# MPPT_Charger_12A.net
KiCad netlist of a schematic drawn in EAGLE
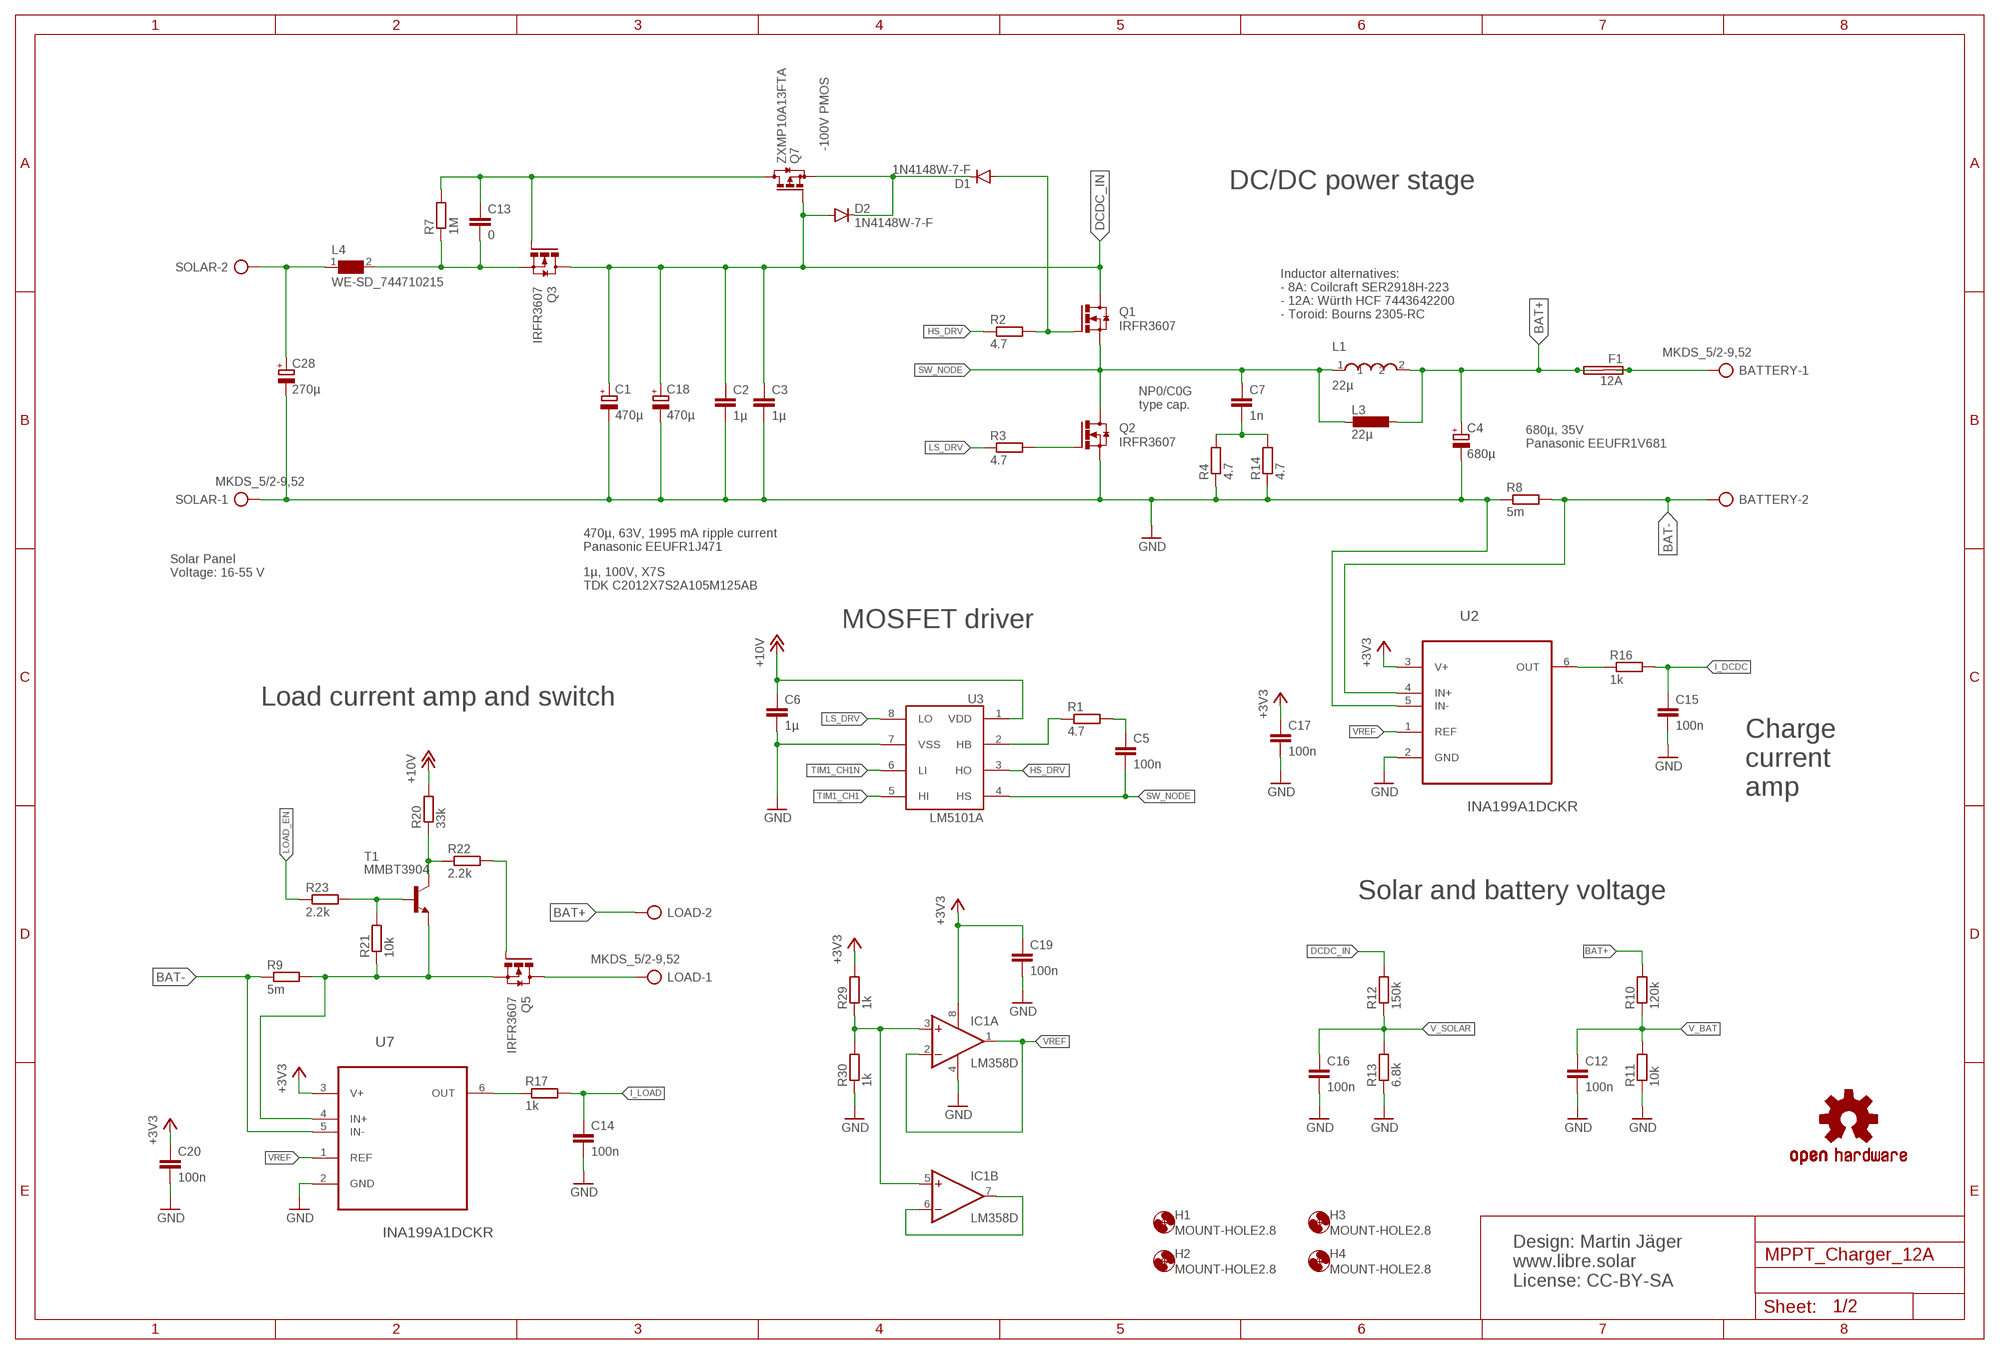
[diagram p0: schematic, sheet 1]
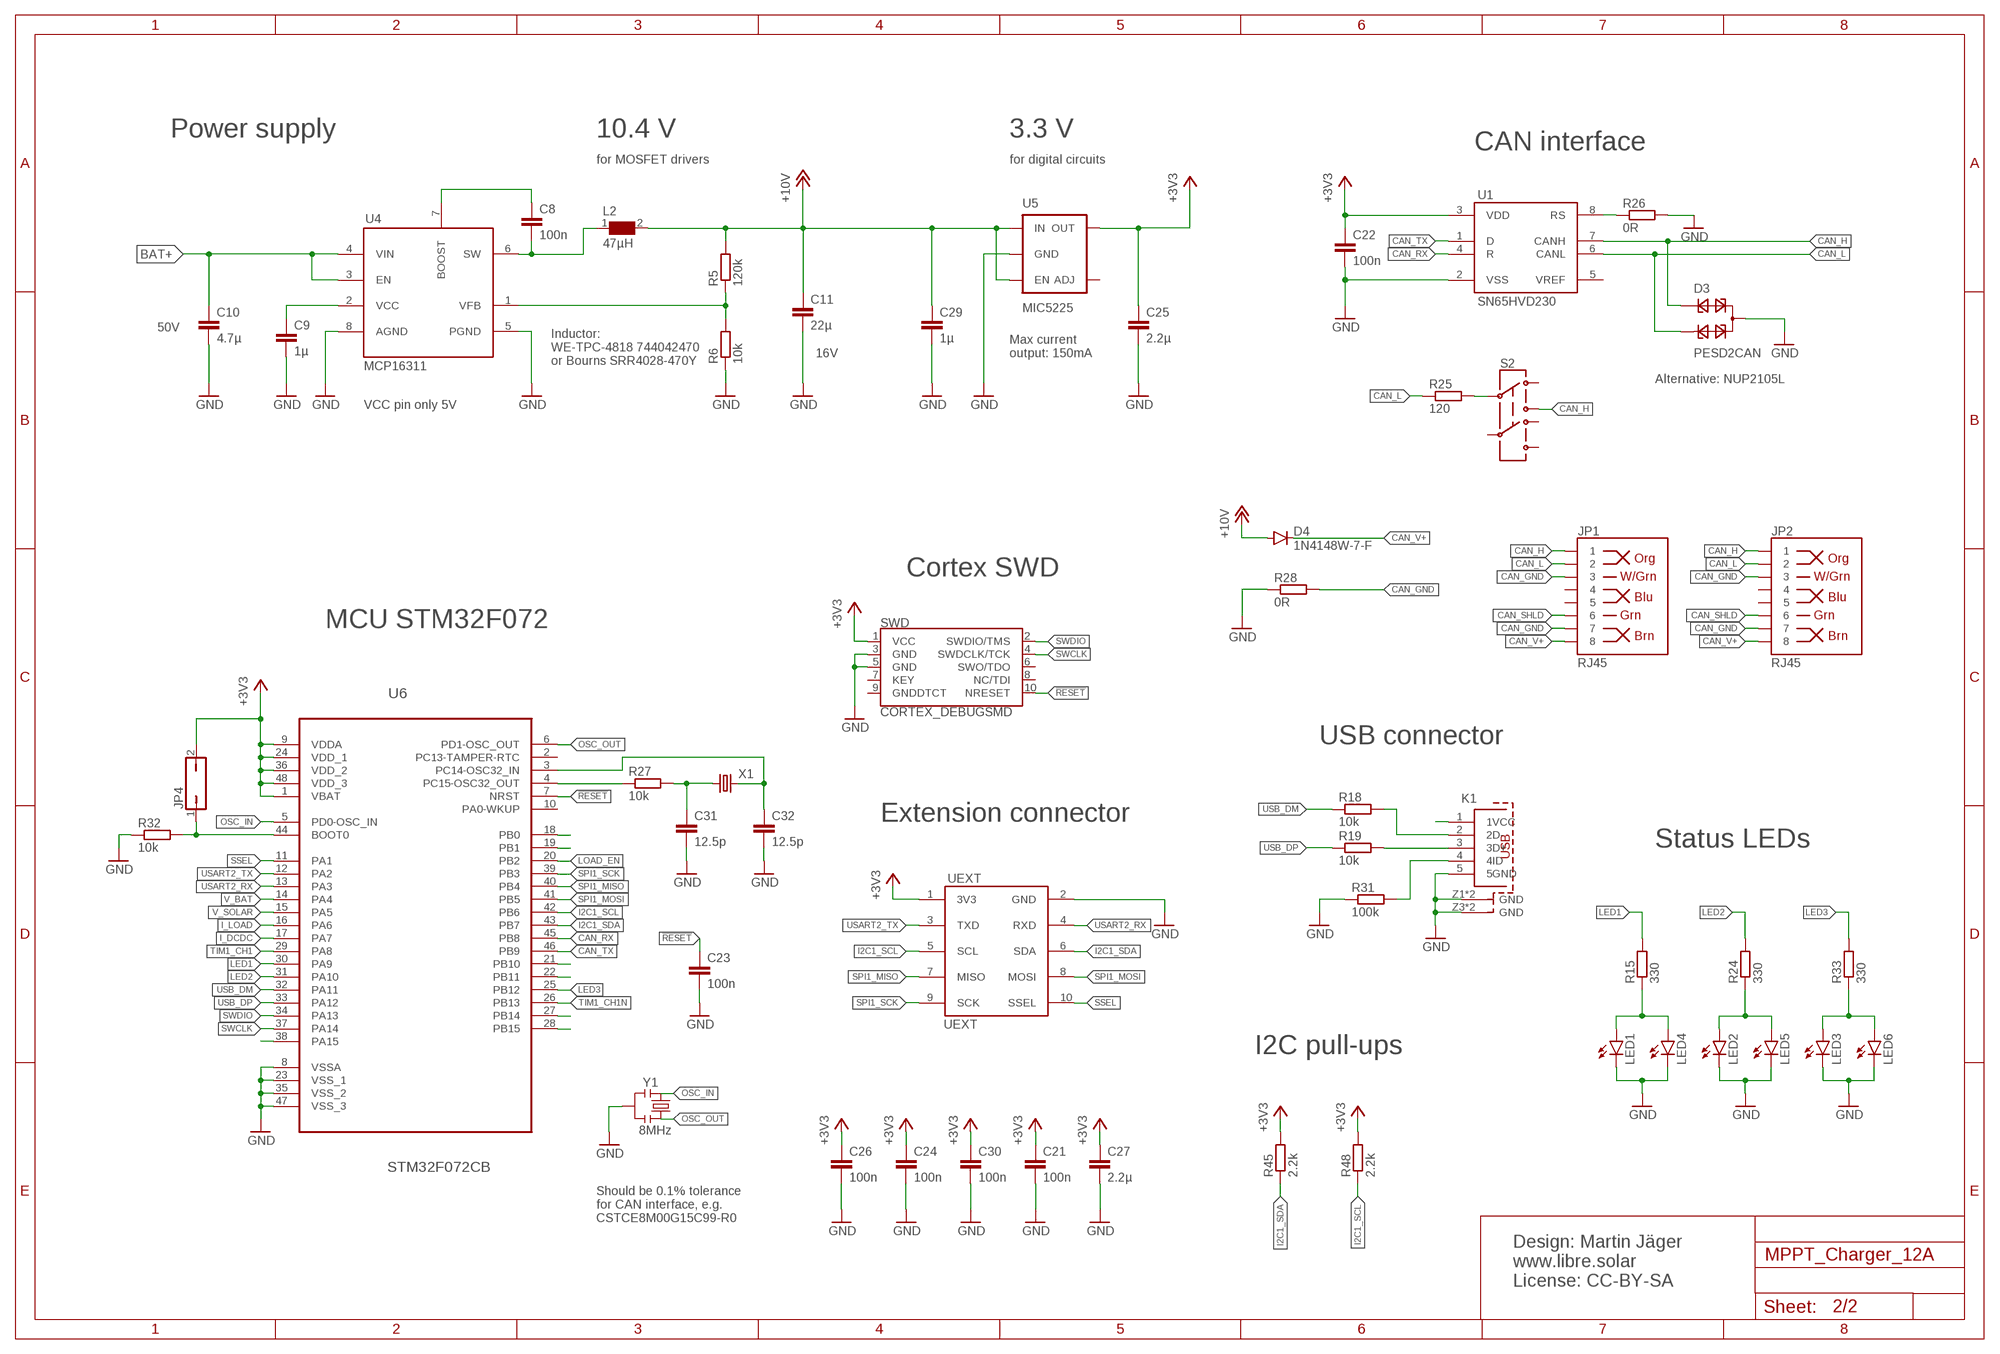
[diagram p1: schematic, sheet 2]

(export (version "E")
  (design (tool "Eeschema 10.0.6"))
  (components
    (comp (ref "C8")
      (value "100n")
      (footprint "eagle-import:C0603")
      (fields (field (name "MF") "MURATA") (field (name "MPN") "GRM188R71H104KA93D"))
      (libsource (lib "eagle-import") (part "C-EUC0603"))
    )
    (comp (ref "C9")
      (value "1µ")
      (footprint "eagle-import:C0603")
      (fields (field (name "MF") "AVX") (field (name "MPN") "08055C104KAT2A"))
      (libsource (lib "eagle-import") (part "C-EUC0603"))
    )
    (comp (ref "C10")
      (value "4.7µ")
      (footprint "eagle-import:C1210")
      (fields (field (name "MF") "MURATA") (field (name "MPN") "GRM31CR71H475KA12L"))
      (libsource (lib "eagle-import") (part "C-EUC1210"))
    )
    (comp (ref "C11")
      (value "22µ")
      (footprint "eagle-import:C1210")
      (fields (field (name "MF") "MULTICOMP") (field (name "MPN") "MC1210B226M160CT"))
      (libsource (lib "eagle-import") (part "C-EUC1210"))
    )
    (comp (ref "C21")
      (value "100n")
      (footprint "eagle-import:C0603")
      (fields (field (name "MF") "MURATA") (field (name "MPN") "GRM188R71H104KA93D"))
      (libsource (lib "eagle-import") (part "C-EUC0603"))
    )
    (comp (ref "C22")
      (value "100n")
      (footprint "eagle-import:C0603")
      (fields (field (name "MF") "AVX") (field (name "MPN") "06035C104KAT2A"))
      (libsource (lib "eagle-import") (part "C-EUC0603"))
    )
    (comp (ref "C23")
      (value "100n")
      (footprint "eagle-import:C0603")
      (fields (field (name "MF") "MURATA") (field (name "MPN") "GRM188R71H104KA93D"))
      (libsource (lib "eagle-import") (part "C-EUC0603"))
    )
    (comp (ref "C24")
      (value "100n")
      (footprint "eagle-import:C0603")
      (fields (field (name "MF") "MURATA") (field (name "MPN") "GRM188R71H104KA93D"))
      (libsource (lib "eagle-import") (part "C-EUC0603"))
    )
    (comp (ref "C25")
      (value "2.2µ")
      (footprint "eagle-import:C0603")
      (fields (field (name "MF") "AVX") (field (name "MPN") "0805YC475KAT2A"))
      (libsource (lib "eagle-import") (part "C-EUC0603"))
    )
    (comp (ref "C26")
      (value "100n")
      (footprint "eagle-import:C0603")
      (fields (field (name "MF") "MURATA") (field (name "MPN") "GRM188R71H104KA93D"))
      (libsource (lib "eagle-import") (part "C-EUC0603"))
    )
    (comp (ref "C27")
      (value "2.2µ")
      (footprint "eagle-import:C0603")
      (fields (field (name "MF") "AVX") (field (name "MPN") "0805YC475KAT2A"))
      (libsource (lib "eagle-import") (part "C-EUC0603"))
    )
    (comp (ref "C29")
      (value "1µ")
      (footprint "eagle-import:C0603")
      (fields (field (name "MF") "AVX") (field (name "MPN") "08055C104KAT2A"))
      (libsource (lib "eagle-import") (part "C-EUC0603"))
    )
    (comp (ref "C30")
      (value "100n")
      (footprint "eagle-import:C0603")
      (fields (field (name "MF") "MURATA") (field (name "MPN") "GRM188R71H104KA93D"))
      (libsource (lib "eagle-import") (part "C-EUC0603"))
    )
    (comp (ref "C31")
      (value "12.5p")
      (footprint "eagle-import:C0603")
      (fields (field (name "MF") "MURATA") (field (name "MPN") "GRM188R71H104KA93D"))
      (libsource (lib "eagle-import") (part "C-EUC0603"))
    )
    (comp (ref "C32")
      (value "12.5p")
      (footprint "eagle-import:C0603")
      (fields (field (name "MF") "MURATA") (field (name "MPN") "GRM188R71H104KA93D"))
      (libsource (lib "eagle-import") (part "C-EUC0603"))
    )
    (comp (ref "D3")
      (value "PESD2CAN")
      (footprint "eagle-import:SOT23")
      (fields (field (name "MF") "NXP"))
      (libsource (lib "eagle-import") (part "PESD2CAN"))
    )
    (comp (ref "D4")
      (value "1N4148W-7-F")
      (footprint "eagle-import:SOD-123")
      (fields (field (name "MF") "MULTICOMP") (field (name "MPN") "1N4148W"))
      (libsource (lib "eagle-import") (part "DIODESOD123"))
    )
    (comp (ref "JP1")
      (value "RJ45")
      (footprint "eagle-import:RJ45-8")
      (fields (field (name "MF") "AMPHENOL COMMERCIAL PRODUCTS") (field (name "MPN") "RJHSE-5080"))
      (libsource (lib "eagle-import") (part "RJ45-8PTH"))
    )
    (comp (ref "JP2")
      (value "RJ45")
      (footprint "eagle-import:RJ45-8")
      (fields (field (name "MF") "AMPHENOL COMMERCIAL PRODUCTS") (field (name "MPN") "RJHSE-5080"))
      (libsource (lib "eagle-import") (part "RJ45-8PTH"))
    )
    (comp (ref "JP4")
      (value "JP1Q")
      (footprint "eagle-import:JP1")
      (libsource (lib "eagle-import") (part "JP1Q"))
    )
    (comp (ref "K1")
      (value "629105150521")
      (footprint "eagle-import:629105150521")
      (libsource (lib "eagle-import") (part "629105150521"))
    )
    (comp (ref "L2")
      (value "47µH")
      (footprint "eagle-import:WE-TPC_4818_4828")
      (fields (field (name "MF") "WURTH ELEKTRONIK") (field (name "MPN") "744043470"))
      (libsource (lib "eagle-import") (part "WE-TPC_4818/4828"))
    )
    (comp (ref "LED1")
      (value "LED3MM")
      (footprint "eagle-import:LED3MM")
      (libsource (lib "eagle-import") (part "LED3MM"))
    )
    (comp (ref "LED2")
      (value "LED3MM")
      (footprint "eagle-import:LED3MM")
      (libsource (lib "eagle-import") (part "LED3MM"))
    )
    (comp (ref "LED3")
      (value "LED3MM")
      (footprint "eagle-import:LED3MM")
      (libsource (lib "eagle-import") (part "LED3MM"))
    )
    (comp (ref "LED4")
      (value "LED0603")
      (footprint "eagle-import:LED-0603")
      (libsource (lib "eagle-import") (part "LED0603"))
    )
    (comp (ref "LED5")
      (value "LED0603")
      (footprint "eagle-import:LED-0603")
      (libsource (lib "eagle-import") (part "LED0603"))
    )
    (comp (ref "LED6")
      (value "LED0603")
      (footprint "eagle-import:LED-0603")
      (libsource (lib "eagle-import") (part "LED0603"))
    )
    (comp (ref "R5")
      (value "120k")
      (footprint "eagle-import:R0603")
      (fields (field (name "MF") "YAGEO (PHYCOMP)") (field (name "MPN") "RC0603FR-07120KL"))
      (libsource (lib "eagle-import") (part "R-EU_R0603"))
    )
    (comp (ref "R6")
      (value "10k")
      (footprint "eagle-import:R0603")
      (fields (field (name "MF") "YAGEO (PHYCOMP)") (field (name "MPN") "RC0603FR-0710KL"))
      (libsource (lib "eagle-import") (part "R-EU_R0603"))
    )
    (comp (ref "R15")
      (value "330")
      (footprint "eagle-import:R0603")
      (fields (field (name "MF") "YAGEO (PHYCOMP)") (field (name "MPN") "RC0603FR-07330RL"))
      (libsource (lib "eagle-import") (part "R-EU_R0603"))
    )
    (comp (ref "R18")
      (value "10k")
      (footprint "eagle-import:R0603")
      (fields (field (name "MF") "YAGEO (PHYCOMP)") (field (name "MPN") "RC0603FR-0710KL"))
      (libsource (lib "eagle-import") (part "R-EU_R0603"))
    )
    (comp (ref "R19")
      (value "10k")
      (footprint "eagle-import:R0603")
      (fields (field (name "MF") "YAGEO (PHYCOMP)") (field (name "MPN") "RC0603FR-0710KL"))
      (libsource (lib "eagle-import") (part "R-EU_R0603"))
    )
    (comp (ref "R24")
      (value "330")
      (footprint "eagle-import:R0603")
      (fields (field (name "MF") "YAGEO (PHYCOMP)") (field (name "MPN") "RC0603FR-07330RL"))
      (libsource (lib "eagle-import") (part "R-EU_R0603"))
    )
    (comp (ref "R25")
      (value "120")
      (footprint "eagle-import:R1206")
      (fields (field (name "MF") "WELWYN") (field (name "MPN") "WCR0805-120RFI"))
      (libsource (lib "eagle-import") (part "R-EU_R1206"))
    )
    (comp (ref "R26")
      (value "0R")
      (footprint "eagle-import:R0603")
      (fields (field (name "MF") "PANASONIC ELECTRONIC COMPONENTS") (field (name "MPN") "ERJ3GEY0R00V"))
      (libsource (lib "eagle-import") (part "R-EU_R0603"))
    )
    (comp (ref "R27")
      (value "10k")
      (footprint "eagle-import:R0603")
      (fields (field (name "MF") "YAGEO (PHYCOMP)") (field (name "MPN") "RC0603FR-0710KL"))
      (libsource (lib "eagle-import") (part "R-EU_R0603"))
    )
    (comp (ref "R28")
      (value "0R")
      (footprint "eagle-import:R0603")
      (fields (field (name "MF") "PANASONIC ELECTRONIC COMPONENTS") (field (name "MPN") "ERJ3GEY0R00V"))
      (libsource (lib "eagle-import") (part "R-EU_R0603"))
    )
    (comp (ref "R31")
      (value "100k")
      (footprint "eagle-import:R0603")
      (fields (field (name "MF") "YAGEO (PHYCOMP)") (field (name "MPN") "RC0603FR-0710KL"))
      (libsource (lib "eagle-import") (part "R-EU_R0603"))
    )
    (comp (ref "R32")
      (value "10k")
      (footprint "eagle-import:R0603")
      (fields (field (name "MF") "YAGEO (PHYCOMP)") (field (name "MPN") "RC0603FR-0710KL"))
      (libsource (lib "eagle-import") (part "R-EU_R0603"))
    )
    (comp (ref "R33")
      (value "330")
      (footprint "eagle-import:R0603")
      (fields (field (name "MF") "YAGEO (PHYCOMP)") (field (name "MPN") "RC0603FR-07330RL"))
      (libsource (lib "eagle-import") (part "R-EU_R0603"))
    )
    (comp (ref "R45")
      (value "2.2k")
      (footprint "eagle-import:R0603")
      (fields (field (name "MF") "YAGEO (PHYCOMP)") (field (name "MPN") "RC0603FR-072K2L."))
      (libsource (lib "eagle-import") (part "R-EU_R0603"))
    )
    (comp (ref "R48")
      (value "2.2k")
      (footprint "eagle-import:R0603")
      (fields (field (name "MF") "YAGEO (PHYCOMP)") (field (name "MPN") "RC0603FR-072K2L."))
      (libsource (lib "eagle-import") (part "R-EU_R0603"))
    )
    (comp (ref "S2")
      (value "SWITCH-DPDT_CK_JS")
      (footprint "eagle-import:SWITCH-CK_JS_THT")
      (fields (field (name "MF") "C & K COMPONENTS") (field (name "MPN") "JS202011CQN"))
      (libsource (lib "eagle-import") (part "SWITCH-DPDT_CK_JS"))
    )
    (comp (ref "SWD")
      (value "CORTEX_DEBUGSMD")
      (footprint "eagle-import:SAMTECH_FTSH-105-01")
      (libsource (lib "eagle-import") (part "CORTEX_DEBUGSMD"))
    )
    (comp (ref "U1")
      (value "SN65HVD230")
      (footprint "eagle-import:SOIC-8-N")
      (fields (field (name "MF") "TEXAS INSTRUMENTS") (field (name "MPN") "SN65HVD230DR"))
      (libsource (lib "eagle-import") (part "SN65HVD230"))
    )
    (comp (ref "U4")
      (value "MCP16311")
      (footprint "eagle-import:MSOP8")
      (fields (field (name "MF") "MICROCHIP") (field (name "MPN") "MCP16311-E/MS"))
      (libsource (lib "eagle-import") (part "MCP16311"))
    )
    (comp (ref "U5")
      (value "MIC5225")
      (footprint "eagle-import:SOT23-5")
      (fields (field (name "MF") "MICROCHIP") (field (name "MPN") "MIC5225-3.3YM5-TR"))
      (libsource (lib "eagle-import") (part "V_REG_MIC5235"))
    )
    (comp (ref "U6")
      (value "STM32F072CB")
      (footprint "eagle-import:QFP50P900X900X160-48N")
      (fields (field (name "MPN") "STM32F100C4T6B"))
      (libsource (lib "eagle-import") (part "STM32F072CB"))
    )
    (comp (ref "UEXT")
      (value "UEXT")
      (footprint "eagle-import:UEXT")
      (libsource (lib "eagle-import") (part "UEXT"))
    )
    (comp (ref "X1")
      (value "CRYSTALMM20SS")
      (footprint "eagle-import:MM20SS")
      (libsource (lib "eagle-import") (part "CRYSTALMM20SS"))
    )
    (comp (ref "Y1")
      (value "8MHz")
      (footprint "eagle-import:RESONATOR-SMD-1_1")
      (fields (field (name "MF") "MURATA") (field (name "MPN") "CSTCE8M00G55-R0"))
      (libsource (lib "eagle-import") (part "RESONATOR1{colon}1"))
    )
    (comp (ref "BATTERY")
      (value "MKDS_5/2-9,52")
      (footprint "eagle-import:MKDS_5_2-952")
      (fields (field (name "OC_FARNELL") "unknown"))
      (libsource (lib "eagle-import") (part "MKDS_5/2-9,52"))
    )
    (comp (ref "C1")
      (value "470µ")
      (footprint "eagle-import:E5-13")
      (fields (field (name "MF") "PANASONIC ELECTRONIC COMPONENTS") (field (name "MPN") "EEUFR1J471B"))
      (libsource (lib "eagle-import") (part "CPOL-EUE5-13"))
    )
    (comp (ref "C2")
      (value "1µ")
      (footprint "eagle-import:C0805")
      (fields (field (name "MF") "TDK") (field (name "MPN") "C2012X7S2A105M125AB"))
      (libsource (lib "eagle-import") (part "C-EUC0805"))
    )
    (comp (ref "C3")
      (value "1µ")
      (footprint "eagle-import:C0805")
      (fields (field (name "MF") "TDK") (field (name "MPN") "C2012X7S2A105M125AB"))
      (libsource (lib "eagle-import") (part "C-EUC0805"))
    )
    (comp (ref "C4")
      (value "680µ")
      (footprint "eagle-import:E5-10,5")
      (fields (field (name "MF") "PANASONIC ELECTRONIC COMPONENTS") (field (name "MPN") "EEUFR1V681LB"))
      (libsource (lib "eagle-import") (part "CPOL-EUE5-10.5"))
    )
    (comp (ref "C5")
      (value "100n")
      (footprint "eagle-import:C0603")
      (fields (field (name "MF") "MURATA") (field (name "MPN") "GRM188R71H104KA93D"))
      (libsource (lib "eagle-import") (part "C-EUC0603"))
    )
    (comp (ref "C6")
      (value "1µ")
      (footprint "eagle-import:C0603")
      (fields (field (name "MF") "AVX") (field (name "MPN") "08055C104KAT2A"))
      (libsource (lib "eagle-import") (part "C-EUC0603"))
    )
    (comp (ref "C7")
      (value "1n")
      (footprint "eagle-import:C0805")
      (fields (field (name "MF") "MULTICOMP") (field (name "MPN") "MCU0805C102JCT"))
      (libsource (lib "eagle-import") (part "C-EUC0805"))
    )
    (comp (ref "C12")
      (value "100n")
      (footprint "eagle-import:C0603")
      (fields (field (name "MF") "MURATA") (field (name "MPN") "GRM188R71H104KA93D"))
      (libsource (lib "eagle-import") (part "C-EUC0603"))
    )
    (comp (ref "C13")
      (value "0")
      (footprint "eagle-import:C0603")
      (fields (field (name "MF") "AVX") (field (name "MPN") "08055C104KAT2A"))
      (libsource (lib "eagle-import") (part "C-EUC0603"))
    )
    (comp (ref "C14")
      (value "100n")
      (footprint "eagle-import:C0603")
      (fields (field (name "MF") "MURATA") (field (name "MPN") "GRM188R71H104KA93D"))
      (libsource (lib "eagle-import") (part "C-EUC0603"))
    )
    (comp (ref "C15")
      (value "100n")
      (footprint "eagle-import:C0603")
      (fields (field (name "MF") "MURATA") (field (name "MPN") "GRM188R71H104KA93D"))
      (libsource (lib "eagle-import") (part "C-EUC0603"))
    )
    (comp (ref "C16")
      (value "100n")
      (footprint "eagle-import:C0603")
      (fields (field (name "MF") "MURATA") (field (name "MPN") "GRM188R71H104KA93D"))
      (libsource (lib "eagle-import") (part "C-EUC0603"))
    )
    (comp (ref "C17")
      (value "100n")
      (footprint "eagle-import:C0603")
      (fields (field (name "MF") "MURATA") (field (name "MPN") "GRM188R71H104KA93D"))
      (libsource (lib "eagle-import") (part "C-EUC0603"))
    )
    (comp (ref "C18")
      (value "470µ")
      (footprint "eagle-import:E5-13")
      (fields (field (name "MF") "PANASONIC ELECTRONIC COMPONENTS") (field (name "MPN") "EEUFR1J471B"))
      (libsource (lib "eagle-import") (part "CPOL-EUE5-13"))
    )
    (comp (ref "C19")
      (value "100n")
      (footprint "eagle-import:C0603")
      (fields (field (name "MF") "MURATA") (field (name "MPN") "GRM188R71H104KA93D"))
      (libsource (lib "eagle-import") (part "C-EUC0603"))
    )
    (comp (ref "C20")
      (value "100n")
      (footprint "eagle-import:C0603")
      (fields (field (name "MF") "MURATA") (field (name "MPN") "GRM188R71H104KA93D"))
      (libsource (lib "eagle-import") (part "C-EUC0603"))
    )
    (comp (ref "C28")
      (value "270µ")
      (footprint "eagle-import:E5-10,5")
      (fields (field (name "MF") "PANASONIC ELECTRONIC COMPONENTS") (field (name "MPN") "EEUFR1J271LB"))
      (libsource (lib "eagle-import") (part "CPOL-EUE5-10.5"))
    )
    (comp (ref "D1")
      (value "1N4148W-7-F")
      (footprint "eagle-import:SOD-123")
      (fields (field (name "MF") "MULTICOMP") (field (name "MPN") "1N4148W"))
      (libsource (lib "eagle-import") (part "DIODESOD123"))
    )
    (comp (ref "D2")
      (value "1N4148W-7-F")
      (footprint "eagle-import:SOD-123")
      (fields (field (name "MF") "MULTICOMP") (field (name "MPN") "1N4148W"))
      (libsource (lib "eagle-import") (part "DIODESOD123"))
    )
    (comp (ref "F1")
      (value "12A")
      (footprint "eagle-import:BLADE_FUSE_STD")
      (fields (field (name "MF") "KEYSTONE") (field (name "MPN") "3522-2"))
      (libsource (lib "eagle-import") (part "FUSE_BLADE_STD"))
    )
    (comp (ref "H1")
      (value "MOUNT-HOLE2.8")
      (footprint "eagle-import:2,8")
      (libsource (lib "eagle-import") (part "MOUNT-HOLE2.8"))
    )
    (comp (ref "H2")
      (value "MOUNT-HOLE2.8")
      (footprint "eagle-import:2,8")
      (libsource (lib "eagle-import") (part "MOUNT-HOLE2.8"))
    )
    (comp (ref "H3")
      (value "MOUNT-HOLE2.8")
      (footprint "eagle-import:2,8")
      (libsource (lib "eagle-import") (part "MOUNT-HOLE2.8"))
    )
    (comp (ref "H4")
      (value "MOUNT-HOLE2.8")
      (footprint "eagle-import:2,8")
      (libsource (lib "eagle-import") (part "MOUNT-HOLE2.8"))
    )
    (comp (ref "IC1")
      (value "LM358D")
      (footprint "eagle-import:SO08")
      (libsource (lib "eagle-import") (part "LM358D"))
    )
    (comp (ref "L1")
      (value "22µ")
      (footprint "eagle-import:WE-HCF_2818_7443643300")
      (fields (field (name "MF") "COILCRAFT") (field (name "MPN") "SER2918H-223KL"))
      (libsource (lib "eagle-import") (part "WE-HCF_2818_7443643300"))
    )
    (comp (ref "L3")
      (value "22µ")
      (footprint "eagle-import:L-BOURNS-2300-H")
      (fields (field (name "MF") "BOURNS") (field (name "MPN") "2305-V-RC"))
      (libsource (lib "eagle-import") (part "L-BOURNS2300-H"))
    )
    (comp (ref "L4")
      (value "WE-SD_744710215")
      (footprint "eagle-import:WE-SD_744710215")
      (fields (field (name "MF") "WURTH ELEKTRONIK") (field (name "MPN") "744710215"))
      (libsource (lib "eagle-import") (part "WE-SD_744710215"))
    )
    (comp (ref "LOAD")
      (value "MKDS_5/2-9,52")
      (footprint "eagle-import:MKDS_5_2-952")
      (fields (field (name "OC_FARNELL") "unknown"))
      (libsource (lib "eagle-import") (part "MKDS_5/2-9,52"))
    )
    (comp (ref "N1")
      (value "OSHW-LOGOM")
      (footprint "eagle-import:OSHW-LOGO-M")
      (libsource (lib "eagle-import") (part "OSHW-LOGOM"))
    )
    (comp (ref "Q1")
      (value "IRFR3607")
      (footprint "eagle-import:DPAK")
      (fields (field (name "MF") "INTERNATIONAL RECTIFIER") (field (name "MPN") "IRFR3607TRPBF"))
      (libsource (lib "eagle-import") (part "MOSFET_N_DPAK"))
    )
    (comp (ref "Q2")
      (value "IRFR3607")
      (footprint "eagle-import:DPAK")
      (fields (field (name "MF") "INTERNATIONAL RECTIFIER") (field (name "MPN") "IRFR3607TRPBF"))
      (libsource (lib "eagle-import") (part "MOSFET_N_DPAK"))
    )
    (comp (ref "Q3")
      (value "IRFR3607")
      (footprint "eagle-import:DPAK")
      (fields (field (name "MF") "INTERNATIONAL RECTIFIER") (field (name "MPN") "IRFR3607TRPBF"))
      (libsource (lib "eagle-import") (part "MOSFET_N_DPAK"))
    )
    (comp (ref "Q5")
      (value "IRFR3607")
      (footprint "eagle-import:DPAK")
      (fields (field (name "MF") "INTERNATIONAL RECTIFIER") (field (name "MPN") "IRFR3607TRPBF"))
      (libsource (lib "eagle-import") (part "MOSFET_N_DPAK"))
    )
    (comp (ref "Q7")
      (value "ZXMP10A13FTA")
      (footprint "eagle-import:SOT23")
      (fields (field (name "MF") "DIODES INC."))
      (libsource (lib "eagle-import") (part "BSS84"))
    )
    (comp (ref "R1")
      (value "4.7")
      (footprint "eagle-import:R0805")
      (fields (field (name "MF") "BOURNS") (field (name "MPN") "CR0805-FX-1001ELF"))
      (libsource (lib "eagle-import") (part "R-EU_R0805"))
    )
    (comp (ref "R2")
      (value "4.7")
      (footprint "eagle-import:R0805")
      (fields (field (name "MF") "BOURNS") (field (name "MPN") "CR0805-FX-1001ELF"))
      (libsource (lib "eagle-import") (part "R-EU_R0805"))
    )
    (comp (ref "R3")
      (value "4.7")
      (footprint "eagle-import:R0805")
      (fields (field (name "MF") "BOURNS") (field (name "MPN") "CR0805-FX-1001ELF"))
      (libsource (lib "eagle-import") (part "R-EU_R0805"))
    )
    (comp (ref "R4")
      (value "4.7")
      (footprint "eagle-import:R1206")
      (fields (field (name "MF") "YAGEO (PHYCOMP)") (field (name "MPN") "RC1206FR-074R7L"))
      (libsource (lib "eagle-import") (part "R-EU_R1206"))
    )
    (comp (ref "R7")
      (value "1M")
      (footprint "eagle-import:R0603")
      (fields (field (name "MF") "YAGEO (PHYCOMP)") (field (name "MPN") "RC0603FR-071ML"))
      (libsource (lib "eagle-import") (part "R-EU_R0603"))
    )
    (comp (ref "R8")
      (value "5m")
      (footprint "eagle-import:R2512")
      (fields (field (name "MF") "BOURNS") (field (name "MPN") "CRF2512-FX-R005ELF"))
      (libsource (lib "eagle-import") (part "R-EU_R2512"))
    )
    (comp (ref "R9")
      (value "5m")
      (footprint "eagle-import:R2512")
      (fields (field (name "MF") "BOURNS") (field (name "MPN") "CRF2512-FX-R005ELF"))
      (libsource (lib "eagle-import") (part "R-EU_R2512"))
    )
    (comp (ref "R10")
      (value "120k")
      (footprint "eagle-import:R0603")
      (fields (field (name "MF") "YAGEO (PHYCOMP)") (field (name "MPN") "RC0603FR-07120KL"))
      (libsource (lib "eagle-import") (part "R-EU_R0603"))
    )
    (comp (ref "R11")
      (value "10k")
      (footprint "eagle-import:R0603")
      (fields (field (name "MF") "YAGEO (PHYCOMP)") (field (name "MPN") "RC0603FR-0710KL"))
      (libsource (lib "eagle-import") (part "R-EU_R0603"))
    )
    (comp (ref "R12")
      (value "150k")
      (footprint "eagle-import:R0603")
      (fields (field (name "MF") "YAGEO (PHYCOMP)") (field (name "MPN") "RC0603FR-07150KL"))
      (libsource (lib "eagle-import") (part "R-EU_R0603"))
    )
    (comp (ref "R13")
      (value "6.8k")
      (footprint "eagle-import:R0603")
      (fields (field (name "MF") "YAGEO (PHYCOMP)") (field (name "MPN") "RC0603FR-076K8L"))
      (libsource (lib "eagle-import") (part "R-EU_R0603"))
    )
    (comp (ref "R14")
      (value "4.7")
      (footprint "eagle-import:R1206")
      (fields (field (name "MF") "YAGEO (PHYCOMP)") (field (name "MPN") "RC1206FR-074R7L"))
      (libsource (lib "eagle-import") (part "R-EU_R1206"))
    )
    (comp (ref "R16")
      (value "1k")
      (footprint "eagle-import:R0603")
      (fields (field (name "MF") "YAGEO (PHYCOMP)") (field (name "MPN") "RC0603FR-071KL."))
      (libsource (lib "eagle-import") (part "R-EU_R0603"))
    )
    (comp (ref "R17")
      (value "1k")
      (footprint "eagle-import:R0603")
      (fields (field (name "MF") "YAGEO (PHYCOMP)") (field (name "MPN") "RC0603FR-071KL."))
      (libsource (lib "eagle-import") (part "R-EU_R0603"))
    )
    (comp (ref "R20")
      (value "33k")
      (footprint "eagle-import:R0603")
      (fields (field (name "MF") "YAGEO (PHYCOMP)") (field (name "MPN") "RC0603FR-0733KL"))
      (libsource (lib "eagle-import") (part "R-EU_R0603"))
    )
    (comp (ref "R21")
      (value "10k")
      (footprint "eagle-import:R0603")
      (fields (field (name "MF") "YAGEO (PHYCOMP)") (field (name "MPN") "RC0603FR-0710KL"))
      (libsource (lib "eagle-import") (part "R-EU_R0603"))
    )
    (comp (ref "R22")
      (value "2.2k")
      (footprint "eagle-import:R0603")
      (fields (field (name "MF") "YAGEO (PHYCOMP)") (field (name "MPN") "RC0603FR-072K2L."))
      (libsource (lib "eagle-import") (part "R-EU_R0603"))
    )
    (comp (ref "R23")
      (value "2.2k")
      (footprint "eagle-import:R0603")
      (fields (field (name "MF") "YAGEO (PHYCOMP)") (field (name "MPN") "RC0603FR-072K2L."))
      (libsource (lib "eagle-import") (part "R-EU_R0603"))
    )
    (comp (ref "R29")
      (value "1k")
      (footprint "eagle-import:R0603")
      (fields (field (name "MF") "YAGEO (PHYCOMP)") (field (name "MPN") "RC0603FR-071KL."))
      (libsource (lib "eagle-import") (part "R-EU_R0603"))
    )
    (comp (ref "R30")
      (value "1k")
      (footprint "eagle-import:R0603")
      (fields (field (name "MF") "YAGEO (PHYCOMP)") (field (name "MPN") "RC0603FR-071KL."))
      (libsource (lib "eagle-import") (part "R-EU_R0603"))
    )
    (comp (ref "SOLAR")
      (value "MKDS_5/2-9,52")
      (footprint "eagle-import:MKDS_5_2-952")
      (fields (field (name "OC_FARNELL") "unknown"))
      (libsource (lib "eagle-import") (part "MKDS_5/2-9,52"))
    )
    (comp (ref "T1")
      (value "MMBT3904")
      (footprint "eagle-import:SOT23-BEC")
      (fields (field (name "MF") "DIODES INC.") (field (name "MPN") "MMBT3904-7-F"))
      (libsource (lib "eagle-import") (part "-NPN-SOT23-BECMMBT3904LT1"))
    )
    (comp (ref "U2")
      (value "INA199A1DCKR")
      (footprint "eagle-import:SOT65P210X110-6N")
      (libsource (lib "eagle-import") (part "INA199A1DCKR"))
    )
    (comp (ref "U3")
      (value "LM5101A")
      (footprint "eagle-import:SOIC-8-N")
      (fields (field (name "MF") "TEXAS INSTRUMENTS") (field (name "MPN") "LM5101AM/NOPB"))
      (libsource (lib "eagle-import") (part "LM5101A"))
    )
    (comp (ref "U7")
      (value "INA199A1DCKR")
      (footprint "eagle-import:SOT65P210X110-6N")
      (libsource (lib "eagle-import") (part "INA199A1DCKR"))
    )
  )
  (nets
    (net (code "1") (name "+3V3") (class "Default")
      (node (ref "C17") (pin "1") (pinfunction "1_1") (pintype "passive"))
      (node (ref "C19") (pin "1") (pinfunction "1_1") (pintype "passive"))
      (node (ref "C20") (pin "1") (pinfunction "1_1") (pintype "passive"))
      (node (ref "C21") (pin "1") (pinfunction "1_1") (pintype "passive"))
      (node (ref "C22") (pin "1") (pinfunction "1_1") (pintype "passive"))
      (node (ref "C24") (pin "1") (pinfunction "1_1") (pintype "passive"))
      (node (ref "C25") (pin "1") (pinfunction "1_1") (pintype "passive"))
      (node (ref "C26") (pin "1") (pinfunction "1_1") (pintype "passive"))
      (node (ref "C27") (pin "1") (pinfunction "1_1") (pintype "passive"))
      (node (ref "C30") (pin "1") (pinfunction "1_1") (pintype "passive"))
      (node (ref "IC1") (pin "8") (pinfunction "V+_8") (pintype "power_in"))
      (node (ref "JP4") (pin "2") (pinfunction "2_2") (pintype "passive"))
      (node (ref "R29") (pin "2") (pinfunction "2_2") (pintype "passive"))
      (node (ref "R45") (pin "2") (pinfunction "2_2") (pintype "passive"))
      (node (ref "R48") (pin "2") (pinfunction "2_2") (pintype "passive"))
      (node (ref "SWD") (pin "1") (pinfunction "VCC_1") (pintype "bidirectional"))
      (node (ref "U1") (pin "3") (pinfunction "VDD_3") (pintype "power_in"))
      (node (ref "U2") (pin "3") (pinfunction "V+_3") (pintype "power_in"))
      (node (ref "U5") (pin "5") (pinfunction "OUT_5") (pintype "passive"))
      (node (ref "U6") (pin "1") (pinfunction "VBAT_1") (pintype "power_in"))
      (node (ref "U6") (pin "24") (pinfunction "VDD_1_24") (pintype "power_in"))
      (node (ref "U6") (pin "36") (pinfunction "VDD_2_36") (pintype "power_in"))
      (node (ref "U6") (pin "48") (pinfunction "VDD_3_48") (pintype "power_in"))
      (node (ref "U6") (pin "9") (pinfunction "VDDA_9") (pintype "power_in"))
      (node (ref "U7") (pin "3") (pinfunction "V+_3") (pintype "power_in"))
      (node (ref "UEXT") (pin "1") (pinfunction "3V3_1") (pintype "passive"))
    )
    (net (code "2") (name "+10V") (class "Default")
      (node (ref "C11") (pin "1") (pinfunction "1_1") (pintype "passive"))
      (node (ref "C29") (pin "1") (pinfunction "1_1") (pintype "passive"))
      (node (ref "C6") (pin "1") (pinfunction "1_1") (pintype "passive"))
      (node (ref "D4") (pin "A") (pinfunction "A_A") (pintype "passive"))
      (node (ref "L2") (pin "2") (pinfunction "2_2") (pintype "passive"))
      (node (ref "R20") (pin "2") (pinfunction "2_2") (pintype "passive"))
      (node (ref "R5") (pin "2") (pinfunction "2_2") (pintype "passive"))
      (node (ref "U3") (pin "1") (pinfunction "VDD_1") (pintype "power_in"))
      (node (ref "U5") (pin "1") (pinfunction "IN_1") (pintype "input"))
      (node (ref "U5") (pin "3") (pinfunction "EN_3") (pintype "input"))
    )
    (net (code "3") (name "BAT+") (class "Default")
      (node (ref "C10") (pin "1") (pinfunction "1_1") (pintype "passive"))
      (node (ref "C4") (pin "+") (pinfunction "+_+") (pintype "passive"))
      (node (ref "F1") (pin "P$3") (pinfunction "2A_P$3") (pintype "passive"))
      (node (ref "F1") (pin "P$4") (pinfunction "2B_P$4") (pintype "passive"))
      (node (ref "L1") (pin "2") (pinfunction "2_2") (pintype "bidirectional"))
      (node (ref "L3") (pin "P$1") (pinfunction "1_P$1") (pintype "passive"))
      (node (ref "LOAD") (pin "2") (pinfunction "KL_2") (pintype "passive"))
      (node (ref "R10") (pin "2") (pinfunction "2_2") (pintype "passive"))
      (node (ref "U4") (pin "3") (pinfunction "EN_3") (pintype "bidirectional"))
      (node (ref "U4") (pin "4") (pinfunction "VIN_4") (pintype "bidirectional"))
    )
    (net (code "4") (name "BAT-") (class "Default")
      (node (ref "BATTERY") (pin "2") (pinfunction "KL_2") (pintype "passive"))
      (node (ref "R8") (pin "2") (pinfunction "2_2") (pintype "passive"))
      (node (ref "R9") (pin "1") (pinfunction "1_1") (pintype "passive"))
      (node (ref "U2") (pin "4") (pinfunction "IN+_4") (pintype "input"))
      (node (ref "U7") (pin "5") (pinfunction "IN-_5") (pintype "input"))
    )
    (net (code "5") (name "CAN_GND") (class "Default")
      (node (ref "JP1") (pin "3") (pinfunction "3_3") (pintype "bidirectional"))
      (node (ref "JP1") (pin "7") (pinfunction "7_7") (pintype "bidirectional"))
      (node (ref "JP2") (pin "3") (pinfunction "3_3") (pintype "bidirectional"))
      (node (ref "JP2") (pin "7") (pinfunction "7_7") (pintype "bidirectional"))
      (node (ref "R28") (pin "2") (pinfunction "2_2") (pintype "passive"))
    )
    (net (code "6") (name "CAN_H") (class "Default")
      (node (ref "D3") (pin "1") (pinfunction "1_1") (pintype "passive"))
      (node (ref "JP1") (pin "1") (pinfunction "1_1") (pintype "bidirectional"))
      (node (ref "JP2") (pin "1") (pinfunction "1_1") (pintype "bidirectional"))
      (node (ref "S2") (pin "P$3") (pinfunction "3_P$3") (pintype "bidirectional"))
      (node (ref "U1") (pin "7") (pinfunction "CANH_7") (pintype "bidirectional"))
    )
    (net (code "7") (name "CAN_L") (class "Default")
      (node (ref "D3") (pin "2") (pinfunction "2_2") (pintype "passive"))
      (node (ref "JP1") (pin "2") (pinfunction "2_2") (pintype "bidirectional"))
      (node (ref "JP2") (pin "2") (pinfunction "2_2") (pintype "bidirectional"))
      (node (ref "R25") (pin "1") (pinfunction "1_1") (pintype "passive"))
      (node (ref "U1") (pin "6") (pinfunction "CANL_6") (pintype "bidirectional"))
    )
    (net (code "8") (name "CAN_RX") (class "Default")
      (node (ref "U1") (pin "4") (pinfunction "R_4") (pintype "output"))
      (node (ref "U6") (pin "45") (pinfunction "PB8_45") (pintype "bidirectional"))
    )
    (net (code "9") (name "CAN_SHLD") (class "Default")
      (node (ref "JP1") (pin "6") (pinfunction "6_6") (pintype "bidirectional"))
      (node (ref "JP2") (pin "6") (pinfunction "6_6") (pintype "bidirectional"))
    )
    (net (code "10") (name "CAN_TX") (class "Default")
      (node (ref "U1") (pin "1") (pinfunction "D_1") (pintype "input"))
      (node (ref "U6") (pin "46") (pinfunction "PB9_46") (pintype "bidirectional"))
    )
    (net (code "11") (name "CAN_V+") (class "Default")
      (node (ref "D4") (pin "C") (pinfunction "C_C") (pintype "passive"))
      (node (ref "JP1") (pin "8") (pinfunction "8_8") (pintype "bidirectional"))
      (node (ref "JP2") (pin "8") (pinfunction "8_8") (pintype "bidirectional"))
    )
    (net (code "12") (name "DCDC_IN") (class "Default")
      (node (ref "C1") (pin "+") (pinfunction "+_+") (pintype "passive"))
      (node (ref "C18") (pin "+") (pinfunction "+_+") (pintype "passive"))
      (node (ref "C2") (pin "1") (pinfunction "1_1") (pintype "passive"))
      (node (ref "C3") (pin "1") (pinfunction "1_1") (pintype "passive"))
      (node (ref "D2") (pin "A") (pinfunction "A_A") (pintype "passive"))
      (node (ref "Q1") (pin "4") (pinfunction "D_4") (pintype "passive"))
      (node (ref "Q3") (pin "4") (pinfunction "D_4") (pintype "passive"))
      (node (ref "Q7") (pin "1") (pinfunction "G_1") (pintype "passive"))
      (node (ref "R12") (pin "2") (pinfunction "2_2") (pintype "passive"))
    )
    (net (code "13") (name "GND") (class "Default")
      (node (ref "C1") (pin "-") (pinfunction "-_-") (pintype "passive"))
      (node (ref "C10") (pin "2") (pinfunction "2_2") (pintype "passive"))
      (node (ref "C11") (pin "2") (pinfunction "2_2") (pintype "passive"))
      (node (ref "C12") (pin "2") (pinfunction "2_2") (pintype "passive"))
      (node (ref "C14") (pin "2") (pinfunction "2_2") (pintype "passive"))
      (node (ref "C15") (pin "2") (pinfunction "2_2") (pintype "passive"))
      (node (ref "C16") (pin "2") (pinfunction "2_2") (pintype "passive"))
      (node (ref "C17") (pin "2") (pinfunction "2_2") (pintype "passive"))
      (node (ref "C18") (pin "-") (pinfunction "-_-") (pintype "passive"))
      (node (ref "C19") (pin "2") (pinfunction "2_2") (pintype "passive"))
      (node (ref "C2") (pin "2") (pinfunction "2_2") (pintype "passive"))
      (node (ref "C20") (pin "2") (pinfunction "2_2") (pintype "passive"))
      (node (ref "C21") (pin "2") (pinfunction "2_2") (pintype "passive"))
      (node (ref "C22") (pin "2") (pinfunction "2_2") (pintype "passive"))
      (node (ref "C23") (pin "2") (pinfunction "2_2") (pintype "passive"))
      (node (ref "C24") (pin "2") (pinfunction "2_2") (pintype "passive"))
      (node (ref "C25") (pin "2") (pinfunction "2_2") (pintype "passive"))
      (node (ref "C26") (pin "2") (pinfunction "2_2") (pintype "passive"))
      (node (ref "C27") (pin "2") (pinfunction "2_2") (pintype "passive"))
      (node (ref "C28") (pin "-") (pinfunction "-_-") (pintype "passive"))
      (node (ref "C29") (pin "2") (pinfunction "2_2") (pintype "passive"))
      (node (ref "C3") (pin "2") (pinfunction "2_2") (pintype "passive"))
      (node (ref "C30") (pin "2") (pinfunction "2_2") (pintype "passive"))
      (node (ref "C31") (pin "2") (pinfunction "2_2") (pintype "passive"))
      (node (ref "C32") (pin "2") (pinfunction "2_2") (pintype "passive"))
      (node (ref "C4") (pin "-") (pinfunction "-_-") (pintype "passive"))
      (node (ref "C6") (pin "2") (pinfunction "2_2") (pintype "passive"))
      (node (ref "C9") (pin "2") (pinfunction "2_2") (pintype "passive"))
      (node (ref "D3") (pin "3") (pinfunction "3_3") (pintype "passive"))
      (node (ref "IC1") (pin "4") (pinfunction "V-_4") (pintype "power_in"))
      (node (ref "K1") (pin "5") (pinfunction "5GND_5") (pintype "passive"))
      (node (ref "K1") (pin "Z1") (pinfunction "GND_Z1") (pintype "bidirectional"))
      (node (ref "K1") (pin "Z2") (pinfunction "GND_Z2") (pintype "bidirectional"))
      (node (ref "K1") (pin "Z3") (pinfunction "GND_Z3") (pintype "bidirectional"))
      (node (ref "K1") (pin "Z4") (pinfunction "GND_Z4") (pintype "bidirectional"))
      (node (ref "LED1") (pin "K") (pinfunction "C_K") (pintype "passive"))
      (node (ref "LED2") (pin "K") (pinfunction "C_K") (pintype "passive"))
      (node (ref "LED3") (pin "K") (pinfunction "C_K") (pintype "passive"))
      (node (ref "LED4") (pin "C") (pinfunction "C_C") (pintype "passive"))
      (node (ref "LED5") (pin "C") (pinfunction "C_C") (pintype "passive"))
      (node (ref "LED6") (pin "C") (pinfunction "C_C") (pintype "passive"))
      (node (ref "Q2") (pin "3") (pinfunction "S_3") (pintype "passive"))
      (node (ref "R11") (pin "1") (pinfunction "1_1") (pintype "passive"))
      (node (ref "R13") (pin "1") (pinfunction "1_1") (pintype "passive"))
      (node (ref "R14") (pin "1") (pinfunction "1_1") (pintype "passive"))
      (node (ref "R26") (pin "2") (pinfunction "2_2") (pintype "passive"))
      (node (ref "R28") (pin "1") (pinfunction "1_1") (pintype "passive"))
      (node (ref "R30") (pin "1") (pinfunction "1_1") (pintype "passive"))
      (node (ref "R31") (pin "1") (pinfunction "1_1") (pintype "passive"))
      (node (ref "R32") (pin "1") (pinfunction "1_1") (pintype "passive"))
      (node (ref "R4") (pin "1") (pinfunction "1_1") (pintype "passive"))
      (node (ref "R6") (pin "1") (pinfunction "1_1") (pintype "passive"))
      (node (ref "R8") (pin "1") (pinfunction "1_1") (pintype "passive"))
      (node (ref "SOLAR") (pin "1") (pinfunction "KL_1") (pintype "passive"))
      (node (ref "SWD") (pin "3") (pinfunction "GND_3") (pintype "bidirectional"))
      (node (ref "SWD") (pin "5") (pinfunction "GND_5") (pintype "bidirectional"))
      (node (ref "U1") (pin "2") (pinfunction "VSS_2") (pintype "power_in"))
      (node (ref "U2") (pin "2") (pinfunction "GND_2") (pintype "passive"))
      (node (ref "U2") (pin "5") (pinfunction "IN-_5") (pintype "input"))
      (node (ref "U3") (pin "7") (pinfunction "VSS_7") (pintype "power_in"))
      (node (ref "U4") (pin "5") (pinfunction "PGND_5") (pintype "bidirectional"))
      (node (ref "U4") (pin "8") (pinfunction "AGND_8") (pintype "bidirectional"))
      (node (ref "U5") (pin "2") (pinfunction "GND_2") (pintype "input"))
      (node (ref "U6") (pin "23") (pinfunction "VSS_1_23") (pintype "power_in"))
      (node (ref "U6") (pin "35") (pinfunction "VSS_2_35") (pintype "power_in"))
      (node (ref "U6") (pin "47") (pinfunction "VSS_3_47") (pintype "power_in"))
      (node (ref "U6") (pin "8") (pinfunction "VSSA_8") (pintype "power_in"))
      (node (ref "U7") (pin "2") (pinfunction "GND_2") (pintype "passive"))
      (node (ref "UEXT") (pin "2") (pinfunction "GND_2") (pintype "passive"))
      (node (ref "Y1") (pin "2") (pinfunction "2_2") (pintype "passive"))
    )
    (net (code "14") (name "HS_DRV") (class "Default")
      (node (ref "R2") (pin "1") (pinfunction "1_1") (pintype "passive"))
      (node (ref "U3") (pin "3") (pinfunction "HO_3") (pintype "output"))
    )
    (net (code "15") (name "I2C1_SCL") (class "Default")
      (node (ref "R48") (pin "1") (pinfunction "1_1") (pintype "passive"))
      (node (ref "U6") (pin "42") (pinfunction "PB6_42") (pintype "bidirectional"))
      (node (ref "UEXT") (pin "5") (pinfunction "SCL_5") (pintype "passive"))
    )
    (net (code "16") (name "I2C1_SDA") (class "Default")
      (node (ref "R45") (pin "1") (pinfunction "1_1") (pintype "passive"))
      (node (ref "U6") (pin "43") (pinfunction "PB7_43") (pintype "bidirectional"))
      (node (ref "UEXT") (pin "6") (pinfunction "SDA_6") (pintype "passive"))
    )
    (net (code "17") (name "I_DCDC") (class "Default")
      (node (ref "C15") (pin "1") (pinfunction "1_1") (pintype "passive"))
      (node (ref "R16") (pin "2") (pinfunction "2_2") (pintype "passive"))
      (node (ref "U6") (pin "17") (pinfunction "PA7_17") (pintype "bidirectional"))
    )
    (net (code "18") (name "I_LOAD") (class "Default")
      (node (ref "C14") (pin "1") (pinfunction "1_1") (pintype "passive"))
      (node (ref "R17") (pin "2") (pinfunction "2_2") (pintype "passive"))
      (node (ref "U6") (pin "16") (pinfunction "PA6_16") (pintype "bidirectional"))
    )
    (net (code "19") (name "LED1") (class "Default")
      (node (ref "R15") (pin "2") (pinfunction "2_2") (pintype "passive"))
      (node (ref "U6") (pin "30") (pinfunction "PA9_30") (pintype "bidirectional"))
    )
    (net (code "20") (name "LED2") (class "Default")
      (node (ref "R24") (pin "2") (pinfunction "2_2") (pintype "passive"))
      (node (ref "U6") (pin "31") (pinfunction "PA10_31") (pintype "bidirectional"))
    )
    (net (code "21") (name "LED3") (class "Default")
      (node (ref "R33") (pin "2") (pinfunction "2_2") (pintype "passive"))
      (node (ref "U6") (pin "25") (pinfunction "PB12_25") (pintype "bidirectional"))
    )
    (net (code "22") (name "LOAD_EN") (class "Default")
      (node (ref "R23") (pin "1") (pinfunction "1_1") (pintype "passive"))
      (node (ref "U6") (pin "20") (pinfunction "PB2_20") (pintype "bidirectional"))
    )
    (net (code "23") (name "LS_DRV") (class "Default")
      (node (ref "R3") (pin "1") (pinfunction "1_1") (pintype "passive"))
      (node (ref "U3") (pin "8") (pinfunction "LO_8") (pintype "output"))
    )
    (net (code "24") (name "Net-(BATTERYA-KL)") (class "Default")
      (node (ref "BATTERY") (pin "1") (pinfunction "KL_1") (pintype "passive"))
      (node (ref "F1") (pin "P$1") (pinfunction "1A_P$1") (pintype "passive"))
      (node (ref "F1") (pin "P$2") (pinfunction "1B_P$2") (pintype "passive"))
    )
    (net (code "25") (name "Net-(C5-Pad1)") (class "Default")
      (node (ref "C5") (pin "1") (pinfunction "1_1") (pintype "passive"))
      (node (ref "R1") (pin "2") (pinfunction "2_2") (pintype "passive"))
    )
    (net (code "26") (name "Net-(C7-Pad2)") (class "Default")
      (node (ref "C7") (pin "2") (pinfunction "2_2") (pintype "passive"))
      (node (ref "R14") (pin "2") (pinfunction "2_2") (pintype "passive"))
      (node (ref "R4") (pin "2") (pinfunction "2_2") (pintype "passive"))
    )
    (net (code "27") (name "Net-(C31-Pad1)") (class "Default")
      (node (ref "C31") (pin "1") (pinfunction "1_1") (pintype "passive"))
      (node (ref "R27") (pin "2") (pinfunction "2_2") (pintype "passive"))
      (node (ref "X1") (pin "1") (pinfunction "1_1") (pintype "passive"))
    )
    (net (code "28") (name "Net-(IC1A-+IN)") (class "Default")
      (node (ref "IC1") (pin "3") (pinfunction "+IN_3") (pintype "input"))
      (node (ref "IC1") (pin "5") (pinfunction "+IN_5") (pintype "input"))
      (node (ref "R29") (pin "1") (pinfunction "1_1") (pintype "passive"))
      (node (ref "R30") (pin "2") (pinfunction "2_2") (pintype "passive"))
    )
    (net (code "29") (name "Net-(IC1B--IN)") (class "Default")
      (node (ref "IC1") (pin "6") (pinfunction "-IN_6") (pintype "input"))
      (node (ref "IC1") (pin "7") (pinfunction "OUT_7") (pintype "output"))
    )
    (net (code "30") (name "Net-(K1-2D-)") (class "Default")
      (node (ref "K1") (pin "2") (pinfunction "2D-_2") (pintype "passive"))
      (node (ref "R18") (pin "2") (pinfunction "2_2") (pintype "passive"))
    )
    (net (code "31") (name "Net-(K1-3D+)") (class "Default")
      (node (ref "K1") (pin "3") (pinfunction "3D+_3") (pintype "passive"))
      (node (ref "R19") (pin "2") (pinfunction "2_2") (pintype "passive"))
    )
    (net (code "32") (name "Net-(K1-4ID)") (class "Default")
      (node (ref "K1") (pin "4") (pinfunction "4ID_4") (pintype "passive"))
      (node (ref "R31") (pin "2") (pinfunction "2_2") (pintype "passive"))
    )
    (net (code "33") (name "Net-(LED1-PadA)") (class "Default")
      (node (ref "LED1") (pin "A") (pinfunction "A_A") (pintype "passive"))
      (node (ref "LED4") (pin "A") (pinfunction "A_A") (pintype "passive"))
      (node (ref "R15") (pin "1") (pinfunction "1_1") (pintype "passive"))
    )
    (net (code "34") (name "Net-(LED2-PadA)") (class "Default")
      (node (ref "LED2") (pin "A") (pinfunction "A_A") (pintype "passive"))
      (node (ref "LED5") (pin "A") (pinfunction "A_A") (pintype "passive"))
      (node (ref "R24") (pin "1") (pinfunction "1_1") (pintype "passive"))
    )
    (net (code "35") (name "Net-(LED3-PadA)") (class "Default")
      (node (ref "LED3") (pin "A") (pinfunction "A_A") (pintype "passive"))
      (node (ref "LED6") (pin "A") (pinfunction "A_A") (pintype "passive"))
      (node (ref "R33") (pin "1") (pinfunction "1_1") (pintype "passive"))
    )
    (net (code "36") (name "Net-(LOADA-KL)") (class "Default")
      (node (ref "LOAD") (pin "1") (pinfunction "KL_1") (pintype "passive"))
      (node (ref "Q5") (pin "4") (pinfunction "D_4") (pintype "passive"))
    )
    (net (code "37") (name "Net-(Q1-G)") (class "Default")
      (node (ref "D1") (pin "A") (pinfunction "A_A") (pintype "passive"))
      (node (ref "Q1") (pin "1") (pinfunction "G_1") (pintype "passive"))
      (node (ref "R2") (pin "2") (pinfunction "2_2") (pintype "passive"))
    )
    (net (code "38") (name "Net-(Q2-G)") (class "Default")
      (node (ref "Q2") (pin "1") (pinfunction "G_1") (pintype "passive"))
      (node (ref "R3") (pin "2") (pinfunction "2_2") (pintype "passive"))
    )
    (net (code "39") (name "Net-(Q3-G)") (class "Default")
      (node (ref "C13") (pin "1") (pinfunction "1_1") (pintype "passive"))
      (node (ref "Q3") (pin "1") (pinfunction "G_1") (pintype "passive"))
      (node (ref "Q7") (pin "3") (pinfunction "D_3") (pintype "passive"))
      (node (ref "R7") (pin "2") (pinfunction "2_2") (pintype "passive"))
    )
    (net (code "40") (name "Net-(Q3-S)") (class "Default")
      (node (ref "C13") (pin "2") (pinfunction "2_2") (pintype "passive"))
      (node (ref "L4") (pin "2") (pinfunction "2_2") (pintype "passive"))
      (node (ref "Q3") (pin "3") (pinfunction "S_3") (pintype "passive"))
      (node (ref "R7") (pin "1") (pinfunction "1_1") (pintype "passive"))
    )
    (net (code "41") (name "Net-(Q5-G)") (class "Default")
      (node (ref "Q5") (pin "1") (pinfunction "G_1") (pintype "passive"))
      (node (ref "R22") (pin "2") (pinfunction "2_2") (pintype "passive"))
    )
    (net (code "42") (name "Net-(Q5-S)") (class "Default")
      (node (ref "Q5") (pin "3") (pinfunction "S_3") (pintype "passive"))
      (node (ref "R21") (pin "1") (pinfunction "1_1") (pintype "passive"))
      (node (ref "R9") (pin "2") (pinfunction "2_2") (pintype "passive"))
      (node (ref "T1") (pin "E") (pinfunction "E_E") (pintype "passive"))
      (node (ref "U7") (pin "4") (pinfunction "IN+_4") (pintype "input"))
    )
    (net (code "43") (name "Net-(Q7-S)") (class "Default")
      (node (ref "D1") (pin "C") (pinfunction "C_C") (pintype "passive"))
      (node (ref "D2") (pin "C") (pinfunction "C_C") (pintype "passive"))
      (node (ref "Q7") (pin "2") (pinfunction "S_2") (pintype "passive"))
    )
    (net (code "44") (name "Net-(R20-Pad1)") (class "Default")
      (node (ref "R20") (pin "1") (pinfunction "1_1") (pintype "passive"))
      (node (ref "R22") (pin "1") (pinfunction "1_1") (pintype "passive"))
      (node (ref "T1") (pin "C") (pinfunction "C_C") (pintype "passive"))
    )
    (net (code "45") (name "Net-(R21-Pad2)") (class "Default")
      (node (ref "R21") (pin "2") (pinfunction "2_2") (pintype "passive"))
      (node (ref "R23") (pin "2") (pinfunction "2_2") (pintype "passive"))
      (node (ref "T1") (pin "B") (pinfunction "B_B") (pintype "passive"))
    )
    (net (code "46") (name "Net-(S2-2)") (class "Default")
      (node (ref "R25") (pin "2") (pinfunction "2_2") (pintype "passive"))
      (node (ref "S2") (pin "P$2") (pinfunction "2_P$2") (pintype "bidirectional"))
    )
    (net (code "47") (name "Net-(SOLARB-KL)") (class "Default")
      (node (ref "C28") (pin "+") (pinfunction "+_+") (pintype "passive"))
      (node (ref "L4") (pin "1") (pinfunction "1_1") (pintype "passive"))
      (node (ref "SOLAR") (pin "2") (pinfunction "KL_2") (pintype "passive"))
    )
    (net (code "48") (name "Net-(U1-RS)") (class "Default")
      (node (ref "R26") (pin "1") (pinfunction "1_1") (pintype "passive"))
      (node (ref "U1") (pin "8") (pinfunction "RS_8") (pintype "input"))
    )
    (net (code "49") (name "Net-(U2-OUT)") (class "Default")
      (node (ref "R16") (pin "1") (pinfunction "1_1") (pintype "passive"))
      (node (ref "U2") (pin "6") (pinfunction "OUT_6") (pintype "output"))
    )
    (net (code "50") (name "Net-(U3-HB)") (class "Default")
      (node (ref "R1") (pin "1") (pinfunction "1_1") (pintype "passive"))
      (node (ref "U3") (pin "2") (pinfunction "HB_2") (pintype "input"))
    )
    (net (code "51") (name "Net-(U4-BOOST)") (class "Default")
      (node (ref "C8") (pin "1") (pinfunction "1_1") (pintype "passive"))
      (node (ref "U4") (pin "7") (pinfunction "BOOST_7") (pintype "bidirectional"))
    )
    (net (code "52") (name "Net-(U4-SW)") (class "Default")
      (node (ref "C8") (pin "2") (pinfunction "2_2") (pintype "passive"))
      (node (ref "L2") (pin "1") (pinfunction "1_1") (pintype "passive"))
      (node (ref "U4") (pin "6") (pinfunction "SW_6") (pintype "bidirectional"))
    )
    (net (code "53") (name "Net-(U4-VCC)") (class "Default")
      (node (ref "C9") (pin "1") (pinfunction "1_1") (pintype "passive"))
      (node (ref "U4") (pin "2") (pinfunction "VCC_2") (pintype "bidirectional"))
    )
    (net (code "54") (name "Net-(U4-VFB)") (class "Default")
      (node (ref "R5") (pin "1") (pinfunction "1_1") (pintype "passive"))
      (node (ref "R6") (pin "2") (pinfunction "2_2") (pintype "passive"))
      (node (ref "U4") (pin "1") (pinfunction "VFB_1") (pintype "bidirectional"))
    )
    (net (code "55") (name "Net-(U6-BOOT0)") (class "Default")
      (node (ref "JP4") (pin "1") (pinfunction "1_1") (pintype "passive"))
      (node (ref "R32") (pin "2") (pinfunction "2_2") (pintype "passive"))
      (node (ref "U6") (pin "44") (pinfunction "BOOT0_44") (pintype "input"))
    )
    (net (code "56") (name "Net-(U6-PC14-OSC32_IN)") (class "Default")
      (node (ref "C32") (pin "1") (pinfunction "1_1") (pintype "passive"))
      (node (ref "U6") (pin "3") (pinfunction "PC14-OSC32_IN_3") (pintype "bidirectional"))
      (node (ref "X1") (pin "4") (pinfunction "2_4") (pintype "passive"))
    )
    (net (code "57") (name "Net-(U6-PC15-OSC32_OUT)") (class "Default")
      (node (ref "R27") (pin "1") (pinfunction "1_1") (pintype "passive"))
      (node (ref "U6") (pin "4") (pinfunction "PC15-OSC32_OUT_4") (pintype "bidirectional"))
    )
    (net (code "58") (name "Net-(U7-OUT)") (class "Default")
      (node (ref "R17") (pin "1") (pinfunction "1_1") (pintype "passive"))
      (node (ref "U7") (pin "6") (pinfunction "OUT_6") (pintype "output"))
    )
    (net (code "59") (name "OSC_IN") (class "Default")
      (node (ref "U6") (pin "5") (pinfunction "PD0-OSC_IN_5") (pintype "input"))
      (node (ref "Y1") (pin "1") (pinfunction "1_1") (pintype "passive"))
    )
    (net (code "60") (name "OSC_OUT") (class "Default")
      (node (ref "U6") (pin "6") (pinfunction "PD1-OSC_OUT_6") (pintype "output"))
      (node (ref "Y1") (pin "3") (pinfunction "3_3") (pintype "passive"))
    )
    (net (code "61") (name "SPI1_MISO") (class "Default")
      (node (ref "U6") (pin "40") (pinfunction "PB4_40") (pintype "bidirectional"))
      (node (ref "UEXT") (pin "7") (pinfunction "MISO_7") (pintype "passive"))
    )
    (net (code "62") (name "SPI1_MOSI") (class "Default")
      (node (ref "U6") (pin "41") (pinfunction "PB5_41") (pintype "bidirectional"))
      (node (ref "UEXT") (pin "8") (pinfunction "MOSI_8") (pintype "passive"))
    )
    (net (code "63") (name "SPI1_SCK") (class "Default")
      (node (ref "U6") (pin "39") (pinfunction "PB3_39") (pintype "bidirectional"))
      (node (ref "UEXT") (pin "9") (pinfunction "SCK_9") (pintype "passive"))
    )
    (net (code "64") (name "SSEL") (class "Default")
      (node (ref "U6") (pin "11") (pinfunction "PA1_11") (pintype "bidirectional"))
      (node (ref "UEXT") (pin "10") (pinfunction "SSEL_10") (pintype "passive"))
    )
    (net (code "65") (name "SWCLK") (class "Default")
      (node (ref "SWD") (pin "4") (pinfunction "SWDCLK/TCK_4") (pintype "bidirectional"))
      (node (ref "U6") (pin "37") (pinfunction "PA14_37") (pintype "bidirectional"))
    )
    (net (code "66") (name "SWDIO") (class "Default")
      (node (ref "SWD") (pin "2") (pinfunction "SWDIO/TMS_2") (pintype "bidirectional"))
      (node (ref "U6") (pin "34") (pinfunction "PA13_34") (pintype "bidirectional"))
    )
    (net (code "67") (name "SW_NODE") (class "Default")
      (node (ref "C5") (pin "2") (pinfunction "2_2") (pintype "passive"))
      (node (ref "C7") (pin "1") (pinfunction "1_1") (pintype "passive"))
      (node (ref "L1") (pin "1") (pinfunction "1_1") (pintype "bidirectional"))
      (node (ref "L3") (pin "P$2") (pinfunction "2_P$2") (pintype "passive"))
      (node (ref "Q1") (pin "3") (pinfunction "S_3") (pintype "passive"))
      (node (ref "Q2") (pin "4") (pinfunction "D_4") (pintype "passive"))
      (node (ref "U3") (pin "4") (pinfunction "HS_4") (pintype "input"))
    )
    (net (code "68") (name "TIM1_CH1") (class "Default")
      (node (ref "U3") (pin "5") (pinfunction "HI_5") (pintype "input"))
      (node (ref "U6") (pin "29") (pinfunction "PA8_29") (pintype "bidirectional"))
    )
    (net (code "69") (name "TIM1_CH1N") (class "Default")
      (node (ref "U3") (pin "6") (pinfunction "LI_6") (pintype "input"))
      (node (ref "U6") (pin "26") (pinfunction "PB13_26") (pintype "bidirectional"))
    )
    (net (code "70") (name "USART2_RX") (class "Default")
      (node (ref "U6") (pin "13") (pinfunction "PA3_13") (pintype "bidirectional"))
      (node (ref "UEXT") (pin "4") (pinfunction "RXD_4") (pintype "passive"))
    )
    (net (code "71") (name "USART2_TX") (class "Default")
      (node (ref "U6") (pin "12") (pinfunction "PA2_12") (pintype "bidirectional"))
      (node (ref "UEXT") (pin "3") (pinfunction "TXD_3") (pintype "passive"))
    )
    (net (code "72") (name "USB_DM") (class "Default")
      (node (ref "R18") (pin "1") (pinfunction "1_1") (pintype "passive"))
      (node (ref "U6") (pin "32") (pinfunction "PA11_32") (pintype "bidirectional"))
    )
    (net (code "73") (name "USB_DP") (class "Default")
      (node (ref "R19") (pin "1") (pinfunction "1_1") (pintype "passive"))
      (node (ref "U6") (pin "33") (pinfunction "PA12_33") (pintype "bidirectional"))
    )
    (net (code "74") (name "VREF") (class "Default")
      (node (ref "IC1") (pin "1") (pinfunction "OUT_1") (pintype "output"))
      (node (ref "IC1") (pin "2") (pinfunction "-IN_2") (pintype "input"))
      (node (ref "U2") (pin "1") (pinfunction "REF_1") (pintype "input"))
      (node (ref "U7") (pin "1") (pinfunction "REF_1") (pintype "input"))
    )
    (net (code "75") (name "V_BAT") (class "Default")
      (node (ref "C12") (pin "1") (pinfunction "1_1") (pintype "passive"))
      (node (ref "R10") (pin "1") (pinfunction "1_1") (pintype "passive"))
      (node (ref "R11") (pin "2") (pinfunction "2_2") (pintype "passive"))
      (node (ref "U6") (pin "14") (pinfunction "PA4_14") (pintype "bidirectional"))
    )
    (net (code "76") (name "V_SOLAR") (class "Default")
      (node (ref "C16") (pin "1") (pinfunction "1_1") (pintype "passive"))
      (node (ref "R12") (pin "1") (pinfunction "1_1") (pintype "passive"))
      (node (ref "R13") (pin "2") (pinfunction "2_2") (pintype "passive"))
      (node (ref "U6") (pin "15") (pinfunction "PA5_15") (pintype "bidirectional"))
    )
    (net (code "77") (name "unconnected-(JP1-Pad4)") (class "Default")
      (node (ref "JP1") (pin "4") (pinfunction "4_4") (pintype "bidirectional"))
    )
    (net (code "78") (name "unconnected-(JP1-Pad5)") (class "Default")
      (node (ref "JP1") (pin "5") (pinfunction "5_5") (pintype "bidirectional"))
    )
    (net (code "79") (name "unconnected-(JP2-Pad4)") (class "Default")
      (node (ref "JP2") (pin "4") (pinfunction "4_4") (pintype "bidirectional"))
    )
    (net (code "80") (name "unconnected-(JP2-Pad5)") (class "Default")
      (node (ref "JP2") (pin "5") (pinfunction "5_5") (pintype "bidirectional"))
    )
    (net (code "81") (name "unconnected-(K1-1VCC-Pad1)") (class "Default")
      (node (ref "K1") (pin "1") (pinfunction "1VCC_1") (pintype "passive"))
    )
    (net (code "82") (name "unconnected-(S2-1-PadP$1)") (class "Default")
      (node (ref "S2") (pin "P$1") (pinfunction "1_P$1") (pintype "bidirectional"))
    )
    (net (code "83") (name "unconnected-(S2-4-PadP$4)") (class "Default")
      (node (ref "S2") (pin "P$4") (pinfunction "4_P$4") (pintype "bidirectional"))
    )
    (net (code "84") (name "unconnected-(S2-5-PadP$5)") (class "Default")
      (node (ref "S2") (pin "P$5") (pinfunction "5_P$5") (pintype "bidirectional"))
    )
    (net (code "85") (name "unconnected-(S2-6-PadP$6)") (class "Default")
      (node (ref "S2") (pin "P$6") (pinfunction "6_P$6") (pintype "bidirectional"))
    )
    (net (code "86") (name "unconnected-(SWD-GNDDTCT-Pad9)") (class "Default")
      (node (ref "SWD") (pin "9") (pinfunction "GNDDTCT_9") (pintype "bidirectional"))
    )
    (net (code "87") (name "unconnected-(SWD-KEY-Pad7)") (class "Default")
      (node (ref "SWD") (pin "7") (pinfunction "KEY_7") (pintype "bidirectional"))
    )
    (net (code "88") (name "unconnected-(SWD-NC{slash}TDI-Pad8)") (class "Default")
      (node (ref "SWD") (pin "8") (pinfunction "NC/TDI_8") (pintype "bidirectional"))
    )
    (net (code "89") (name "unconnected-(SWD-SWO{slash}TDO-Pad6)") (class "Default")
      (node (ref "SWD") (pin "6") (pinfunction "SWO/TDO_6") (pintype "bidirectional"))
    )
    (net (code "90") (name "unconnected-(U1-VREF-Pad5)") (class "Default")
      (node (ref "U1") (pin "5") (pinfunction "VREF_5") (pintype "output"))
    )
    (net (code "91") (name "unconnected-(U5-ADJ-Pad4)") (class "Default")
      (node (ref "U5") (pin "4") (pinfunction "ADJ_4") (pintype "input"))
    )
    (net (code "92") (name "unconnected-(U6-PA0-WKUP-Pad10)") (class "Default")
      (node (ref "U6") (pin "10") (pinfunction "PA0-WKUP_10") (pintype "bidirectional"))
    )
    (net (code "93") (name "unconnected-(U6-PA15-Pad38)") (class "Default")
      (node (ref "U6") (pin "38") (pinfunction "PA15_38") (pintype "bidirectional"))
    )
    (net (code "94") (name "unconnected-(U6-PB0-Pad18)") (class "Default")
      (node (ref "U6") (pin "18") (pinfunction "PB0_18") (pintype "bidirectional"))
    )
    (net (code "95") (name "unconnected-(U6-PB1-Pad19)") (class "Default")
      (node (ref "U6") (pin "19") (pinfunction "PB1_19") (pintype "bidirectional"))
    )
    (net (code "96") (name "unconnected-(U6-PB10-Pad21)") (class "Default")
      (node (ref "U6") (pin "21") (pinfunction "PB10_21") (pintype "bidirectional"))
    )
    (net (code "97") (name "unconnected-(U6-PB11-Pad22)") (class "Default")
      (node (ref "U6") (pin "22") (pinfunction "PB11_22") (pintype "bidirectional"))
    )
    (net (code "98") (name "unconnected-(U6-PB14-Pad27)") (class "Default")
      (node (ref "U6") (pin "27") (pinfunction "PB14_27") (pintype "bidirectional"))
    )
    (net (code "99") (name "unconnected-(U6-PB15-Pad28)") (class "Default")
      (node (ref "U6") (pin "28") (pinfunction "PB15_28") (pintype "bidirectional"))
    )
    (net (code "100") (name "unconnected-(U6-PC13-TAMPER-RTC-Pad2)") (class "Default")
      (node (ref "U6") (pin "2") (pinfunction "PC13-TAMPER-RTC_2") (pintype "bidirectional"))
    )
    (net (code "101") (name "~{RESET}") (class "Default")
      (node (ref "C23") (pin "1") (pinfunction "1_1") (pintype "passive"))
      (node (ref "SWD") (pin "10") (pinfunction "NRESET_10") (pintype "bidirectional"))
      (node (ref "U6") (pin "7") (pinfunction "NRST_7") (pintype "bidirectional"))
    )
  )
)
